# Body-Shield.net
KiCad netlist of a schematic drawn in EAGLE
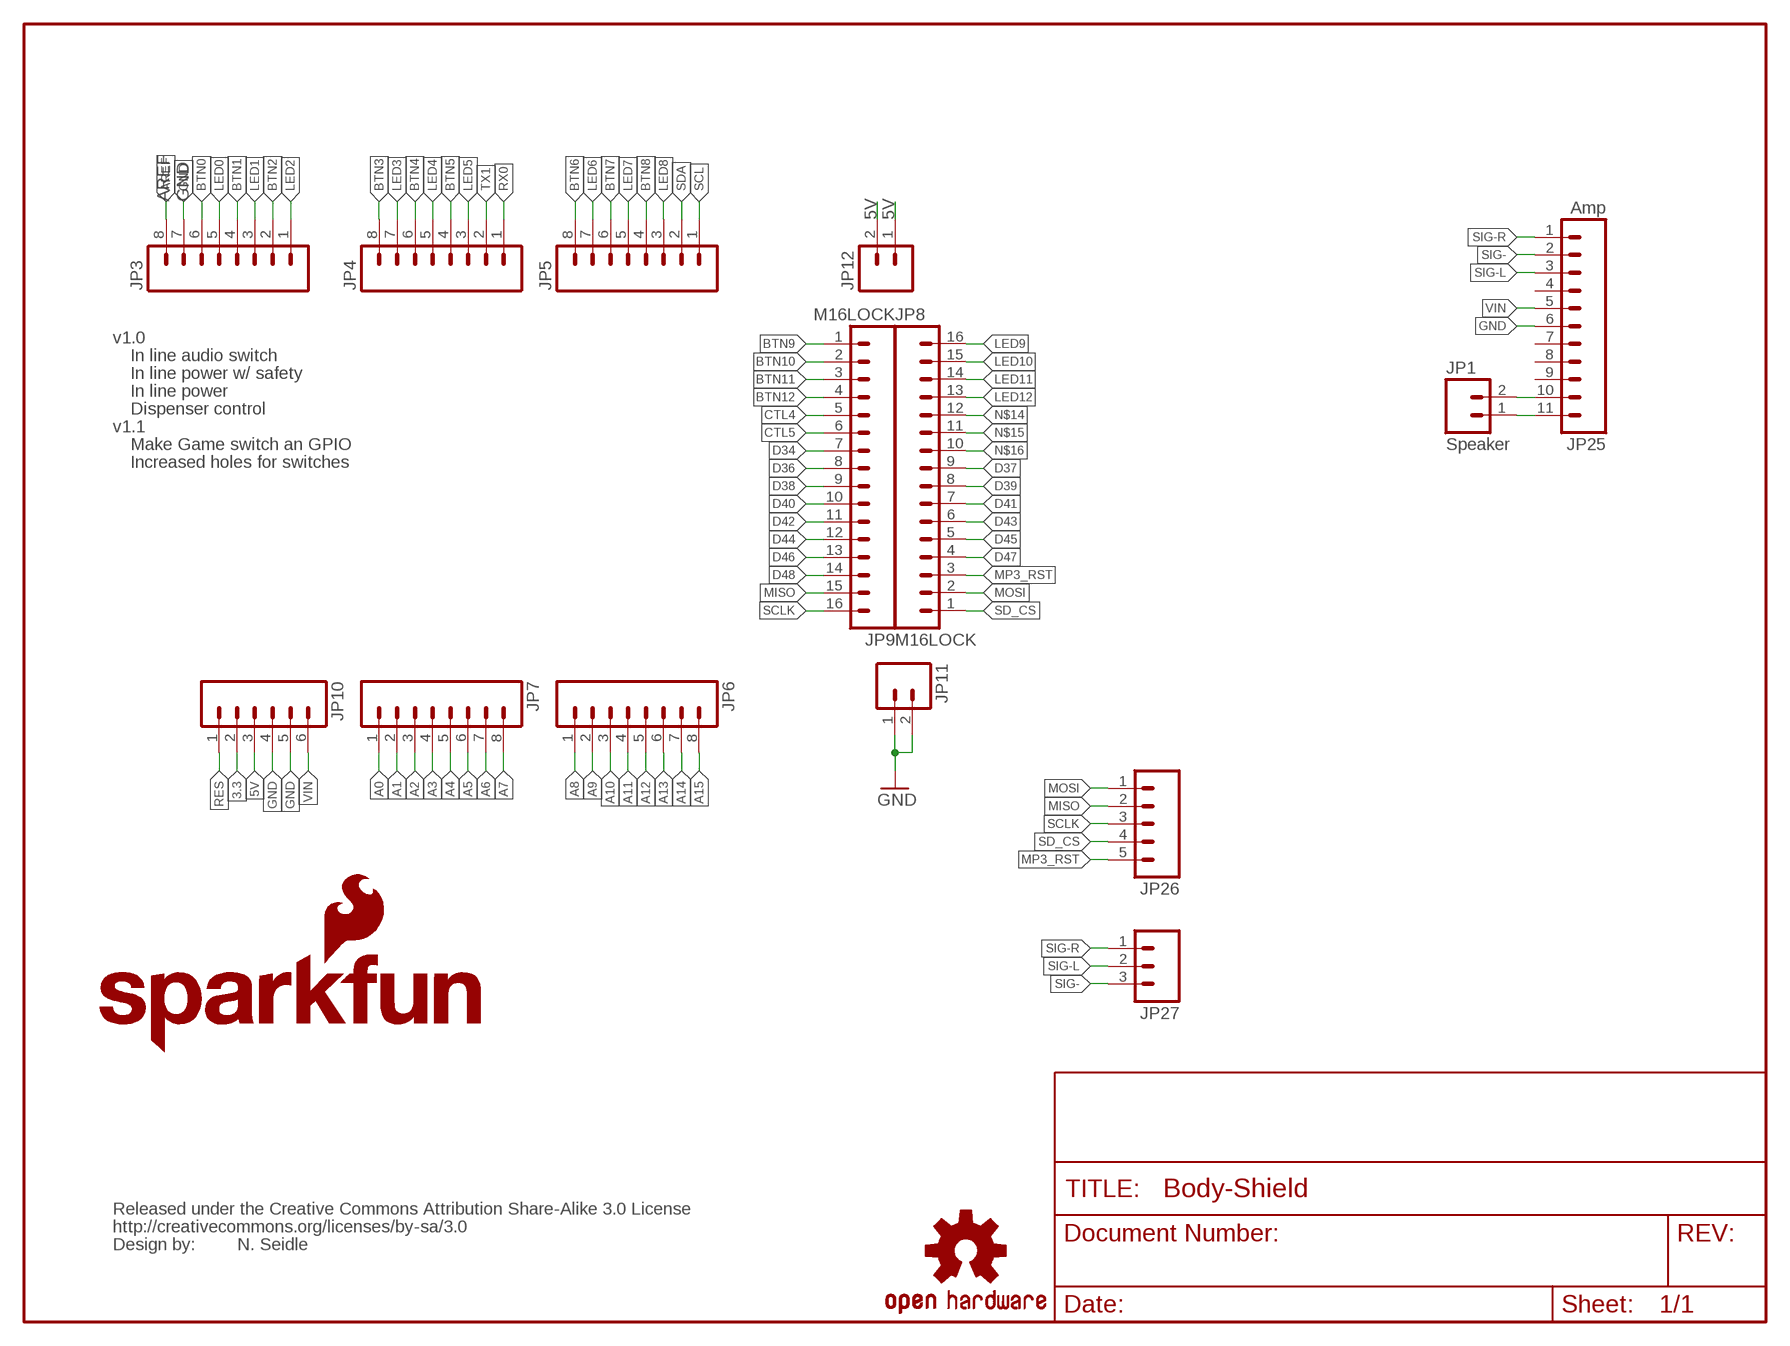
[diagram p0: schematic, sheet 1, part 1 of 2]
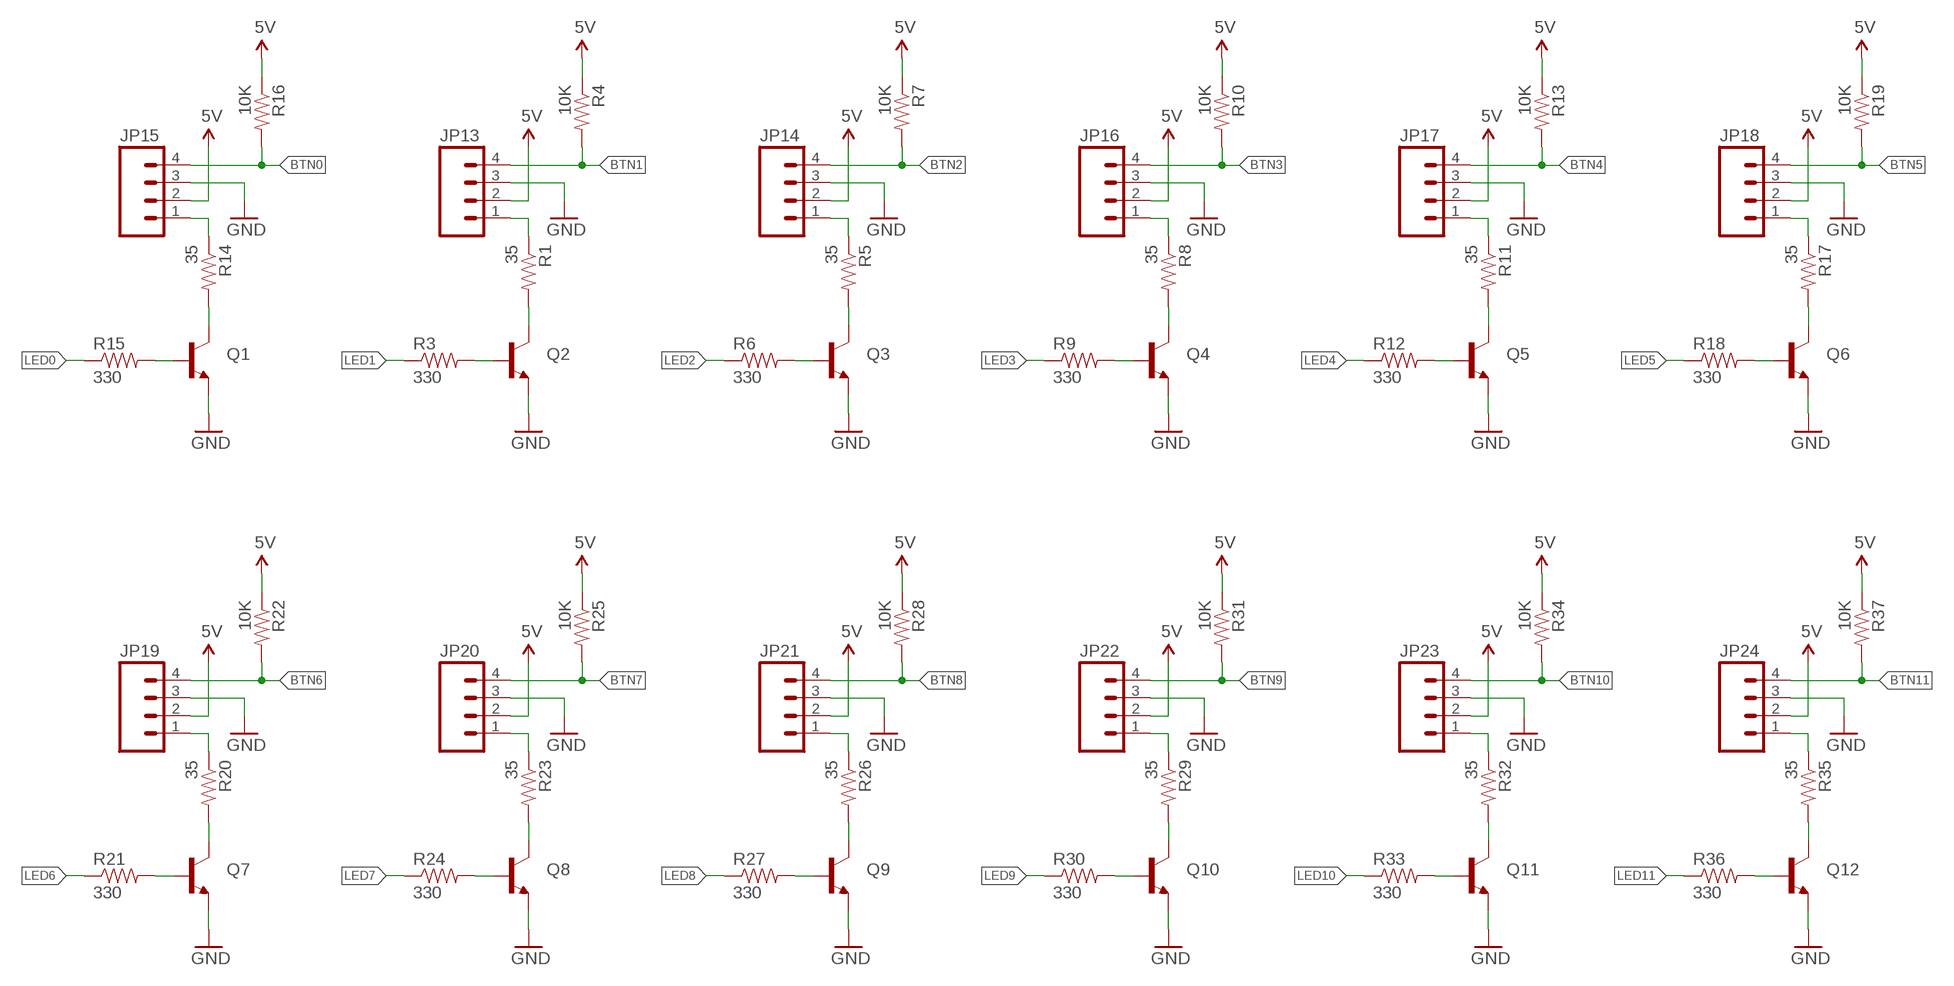
[diagram p1: schematic, sheet 1, part 2 of 2]

(export (version "E")
  (design (tool "Eeschema 10.0.6"))
  (components
    (comp (ref "JP1")
      (value "Speaker")
      (footprint "eagle-import:JST-2-PTH-VERT")
      (libsource (lib "eagle-import") (part "M02JST-PTH-VERT"))
    )
    (comp (ref "JP3")
      (value "M08LOCK")
      (footprint "eagle-import:1X08_LOCK")
      (libsource (lib "eagle-import") (part "M08LOCK"))
    )
    (comp (ref "JP4")
      (value "M08LOCK")
      (footprint "eagle-import:1X08_LOCK")
      (libsource (lib "eagle-import") (part "M08LOCK"))
    )
    (comp (ref "JP5")
      (value "M08LOCK")
      (footprint "eagle-import:1X08_LOCK")
      (libsource (lib "eagle-import") (part "M08LOCK"))
    )
    (comp (ref "JP6")
      (value "M08LOCK")
      (footprint "eagle-import:1X08_LOCK")
      (libsource (lib "eagle-import") (part "M08LOCK"))
    )
    (comp (ref "JP7")
      (value "M08LOCK")
      (footprint "eagle-import:1X08_LOCK")
      (libsource (lib "eagle-import") (part "M08LOCK"))
    )
    (comp (ref "JP8")
      (value "M16LOCK")
      (footprint "eagle-import:1X16_LOCK")
      (libsource (lib "eagle-import") (part "M16LOCK"))
    )
    (comp (ref "JP9")
      (value "M16LOCK")
      (footprint "eagle-import:1X16_LOCK")
      (libsource (lib "eagle-import") (part "M16LOCK"))
    )
    (comp (ref "JP10")
      (value "M06LOCK")
      (footprint "eagle-import:1X06_LOCK")
      (libsource (lib "eagle-import") (part "M06LOCK"))
    )
    (comp (ref "JP11")
      (value "M02LOCK")
      (footprint "eagle-import:1X02_LOCK")
      (libsource (lib "eagle-import") (part "M02LOCK"))
    )
    (comp (ref "JP12")
      (value "M02LOCK")
      (footprint "eagle-import:1X02_LOCK")
      (libsource (lib "eagle-import") (part "M02LOCK"))
    )
    (comp (ref "JP13")
      (value "M04JST-PTH-VERT")
      (footprint "eagle-import:JST-4-PTH-VERT")
      (libsource (lib "eagle-import") (part "M04JST-PTH-VERT"))
    )
    (comp (ref "JP14")
      (value "M04JST-PTH-VERT")
      (footprint "eagle-import:JST-4-PTH-VERT")
      (libsource (lib "eagle-import") (part "M04JST-PTH-VERT"))
    )
    (comp (ref "JP15")
      (value "M04JST-PTH-VERT")
      (footprint "eagle-import:JST-4-PTH-VERT")
      (libsource (lib "eagle-import") (part "M04JST-PTH-VERT"))
    )
    (comp (ref "JP16")
      (value "M04JST-PTH-VERT")
      (footprint "eagle-import:JST-4-PTH-VERT")
      (libsource (lib "eagle-import") (part "M04JST-PTH-VERT"))
    )
    (comp (ref "JP17")
      (value "M04JST-PTH-VERT")
      (footprint "eagle-import:JST-4-PTH-VERT")
      (libsource (lib "eagle-import") (part "M04JST-PTH-VERT"))
    )
    (comp (ref "JP18")
      (value "M04JST-PTH-VERT")
      (footprint "eagle-import:JST-4-PTH-VERT")
      (libsource (lib "eagle-import") (part "M04JST-PTH-VERT"))
    )
    (comp (ref "JP19")
      (value "M04JST-PTH-VERT")
      (footprint "eagle-import:JST-4-PTH-VERT")
      (libsource (lib "eagle-import") (part "M04JST-PTH-VERT"))
    )
    (comp (ref "JP20")
      (value "M04JST-PTH-VERT")
      (footprint "eagle-import:JST-4-PTH-VERT")
      (libsource (lib "eagle-import") (part "M04JST-PTH-VERT"))
    )
    (comp (ref "JP21")
      (value "M04JST-PTH-VERT")
      (footprint "eagle-import:JST-4-PTH-VERT")
      (libsource (lib "eagle-import") (part "M04JST-PTH-VERT"))
    )
    (comp (ref "JP22")
      (value "M04JST-PTH-VERT")
      (footprint "eagle-import:JST-4-PTH-VERT")
      (libsource (lib "eagle-import") (part "M04JST-PTH-VERT"))
    )
    (comp (ref "JP23")
      (value "M04JST-PTH-VERT")
      (footprint "eagle-import:JST-4-PTH-VERT")
      (libsource (lib "eagle-import") (part "M04JST-PTH-VERT"))
    )
    (comp (ref "JP24")
      (value "M04JST-PTH-VERT")
      (footprint "eagle-import:JST-4-PTH-VERT")
      (libsource (lib "eagle-import") (part "M04JST-PTH-VERT"))
    )
    (comp (ref "JP25")
      (value "Amp")
      (footprint "eagle-import:1X11")
      (libsource (lib "eagle-import") (part "M11PTH"))
    )
    (comp (ref "JP26")
      (value "M05JST")
      (footprint "eagle-import:JST-5-PTH")
      (libsource (lib "eagle-import") (part "M05JST"))
    )
    (comp (ref "JP27")
      (value "M03JST-PTH")
      (footprint "eagle-import:JST-3-PTH")
      (libsource (lib "eagle-import") (part "M03JST-PTH"))
    )
    (comp (ref "LOGO1")
      (value "SFE_LOGO_NAME_FLAME.1_INCH")
      (footprint "eagle-import:SFE_LOGO_NAME_FLAME_.1")
      (libsource (lib "eagle-import") (part "SFE_LOGO_NAME_FLAME.1_INCH"))
    )
    (comp (ref "LOGO2")
      (value "OSHW-LOGOS")
      (footprint "eagle-import:OSHW-LOGO-S")
      (libsource (lib "eagle-import") (part "OSHW-LOGOS"))
    )
    (comp (ref "Q1")
      (value "TRANSISTOR_NPN2N3904")
      (footprint "eagle-import:TO-92")
      (libsource (lib "eagle-import") (part "TRANSISTOR_NPN2N3904"))
    )
    (comp (ref "Q2")
      (value "TRANSISTOR_NPN2N3904")
      (footprint "eagle-import:TO-92")
      (libsource (lib "eagle-import") (part "TRANSISTOR_NPN2N3904"))
    )
    (comp (ref "Q3")
      (value "TRANSISTOR_NPN2N3904")
      (footprint "eagle-import:TO-92")
      (libsource (lib "eagle-import") (part "TRANSISTOR_NPN2N3904"))
    )
    (comp (ref "Q4")
      (value "TRANSISTOR_NPN2N3904")
      (footprint "eagle-import:TO-92")
      (libsource (lib "eagle-import") (part "TRANSISTOR_NPN2N3904"))
    )
    (comp (ref "Q5")
      (value "TRANSISTOR_NPN2N3904")
      (footprint "eagle-import:TO-92")
      (libsource (lib "eagle-import") (part "TRANSISTOR_NPN2N3904"))
    )
    (comp (ref "Q6")
      (value "TRANSISTOR_NPN2N3904")
      (footprint "eagle-import:TO-92")
      (libsource (lib "eagle-import") (part "TRANSISTOR_NPN2N3904"))
    )
    (comp (ref "Q7")
      (value "TRANSISTOR_NPN2N3904")
      (footprint "eagle-import:TO-92")
      (libsource (lib "eagle-import") (part "TRANSISTOR_NPN2N3904"))
    )
    (comp (ref "Q8")
      (value "TRANSISTOR_NPN2N3904")
      (footprint "eagle-import:TO-92")
      (libsource (lib "eagle-import") (part "TRANSISTOR_NPN2N3904"))
    )
    (comp (ref "Q9")
      (value "TRANSISTOR_NPN2N3904")
      (footprint "eagle-import:TO-92")
      (libsource (lib "eagle-import") (part "TRANSISTOR_NPN2N3904"))
    )
    (comp (ref "Q10")
      (value "TRANSISTOR_NPN2N3904")
      (footprint "eagle-import:TO-92")
      (libsource (lib "eagle-import") (part "TRANSISTOR_NPN2N3904"))
    )
    (comp (ref "Q11")
      (value "TRANSISTOR_NPN2N3904")
      (footprint "eagle-import:TO-92")
      (libsource (lib "eagle-import") (part "TRANSISTOR_NPN2N3904"))
    )
    (comp (ref "Q12")
      (value "TRANSISTOR_NPN2N3904")
      (footprint "eagle-import:TO-92")
      (libsource (lib "eagle-import") (part "TRANSISTOR_NPN2N3904"))
    )
    (comp (ref "R1")
      (value "35")
      (footprint "eagle-import:AXIAL-0.3")
      (libsource (lib "eagle-import") (part "RESISTORPTH1"))
    )
    (comp (ref "R3")
      (value "330")
      (footprint "eagle-import:AXIAL-0.3")
      (libsource (lib "eagle-import") (part "RESISTORPTH1"))
    )
    (comp (ref "R4")
      (value "10K")
      (footprint "eagle-import:AXIAL-0.3")
      (libsource (lib "eagle-import") (part "RESISTORPTH1"))
    )
    (comp (ref "R5")
      (value "35")
      (footprint "eagle-import:AXIAL-0.3")
      (libsource (lib "eagle-import") (part "RESISTORPTH1"))
    )
    (comp (ref "R6")
      (value "330")
      (footprint "eagle-import:AXIAL-0.3")
      (libsource (lib "eagle-import") (part "RESISTORPTH1"))
    )
    (comp (ref "R7")
      (value "10K")
      (footprint "eagle-import:AXIAL-0.3")
      (libsource (lib "eagle-import") (part "RESISTORPTH1"))
    )
    (comp (ref "R8")
      (value "35")
      (footprint "eagle-import:AXIAL-0.3")
      (libsource (lib "eagle-import") (part "RESISTORPTH1"))
    )
    (comp (ref "R9")
      (value "330")
      (footprint "eagle-import:AXIAL-0.3")
      (libsource (lib "eagle-import") (part "RESISTORPTH1"))
    )
    (comp (ref "R10")
      (value "10K")
      (footprint "eagle-import:AXIAL-0.3")
      (libsource (lib "eagle-import") (part "RESISTORPTH1"))
    )
    (comp (ref "R11")
      (value "35")
      (footprint "eagle-import:AXIAL-0.3")
      (libsource (lib "eagle-import") (part "RESISTORPTH1"))
    )
    (comp (ref "R12")
      (value "330")
      (footprint "eagle-import:AXIAL-0.3")
      (libsource (lib "eagle-import") (part "RESISTORPTH1"))
    )
    (comp (ref "R13")
      (value "10K")
      (footprint "eagle-import:AXIAL-0.3")
      (libsource (lib "eagle-import") (part "RESISTORPTH1"))
    )
    (comp (ref "R14")
      (value "35")
      (footprint "eagle-import:AXIAL-0.3")
      (libsource (lib "eagle-import") (part "RESISTORPTH1"))
    )
    (comp (ref "R15")
      (value "330")
      (footprint "eagle-import:AXIAL-0.3")
      (libsource (lib "eagle-import") (part "RESISTORPTH1"))
    )
    (comp (ref "R16")
      (value "10K")
      (footprint "eagle-import:AXIAL-0.3")
      (libsource (lib "eagle-import") (part "RESISTORPTH1"))
    )
    (comp (ref "R17")
      (value "35")
      (footprint "eagle-import:AXIAL-0.3")
      (libsource (lib "eagle-import") (part "RESISTORPTH1"))
    )
    (comp (ref "R18")
      (value "330")
      (footprint "eagle-import:AXIAL-0.3")
      (libsource (lib "eagle-import") (part "RESISTORPTH1"))
    )
    (comp (ref "R19")
      (value "10K")
      (footprint "eagle-import:AXIAL-0.3")
      (libsource (lib "eagle-import") (part "RESISTORPTH1"))
    )
    (comp (ref "R20")
      (value "35")
      (footprint "eagle-import:AXIAL-0.3")
      (libsource (lib "eagle-import") (part "RESISTORPTH1"))
    )
    (comp (ref "R21")
      (value "330")
      (footprint "eagle-import:AXIAL-0.3")
      (libsource (lib "eagle-import") (part "RESISTORPTH1"))
    )
    (comp (ref "R22")
      (value "10K")
      (footprint "eagle-import:AXIAL-0.3")
      (libsource (lib "eagle-import") (part "RESISTORPTH1"))
    )
    (comp (ref "R23")
      (value "35")
      (footprint "eagle-import:AXIAL-0.3")
      (libsource (lib "eagle-import") (part "RESISTORPTH1"))
    )
    (comp (ref "R24")
      (value "330")
      (footprint "eagle-import:AXIAL-0.3")
      (libsource (lib "eagle-import") (part "RESISTORPTH1"))
    )
    (comp (ref "R25")
      (value "10K")
      (footprint "eagle-import:AXIAL-0.3")
      (libsource (lib "eagle-import") (part "RESISTORPTH1"))
    )
    (comp (ref "R26")
      (value "35")
      (footprint "eagle-import:AXIAL-0.3")
      (libsource (lib "eagle-import") (part "RESISTORPTH1"))
    )
    (comp (ref "R27")
      (value "330")
      (footprint "eagle-import:AXIAL-0.3")
      (libsource (lib "eagle-import") (part "RESISTORPTH1"))
    )
    (comp (ref "R28")
      (value "10K")
      (footprint "eagle-import:AXIAL-0.3")
      (libsource (lib "eagle-import") (part "RESISTORPTH1"))
    )
    (comp (ref "R29")
      (value "35")
      (footprint "eagle-import:AXIAL-0.3")
      (libsource (lib "eagle-import") (part "RESISTORPTH1"))
    )
    (comp (ref "R30")
      (value "330")
      (footprint "eagle-import:AXIAL-0.3")
      (libsource (lib "eagle-import") (part "RESISTORPTH1"))
    )
    (comp (ref "R31")
      (value "10K")
      (footprint "eagle-import:AXIAL-0.3")
      (libsource (lib "eagle-import") (part "RESISTORPTH1"))
    )
    (comp (ref "R32")
      (value "35")
      (footprint "eagle-import:AXIAL-0.3")
      (libsource (lib "eagle-import") (part "RESISTORPTH1"))
    )
    (comp (ref "R33")
      (value "330")
      (footprint "eagle-import:AXIAL-0.3")
      (libsource (lib "eagle-import") (part "RESISTORPTH1"))
    )
    (comp (ref "R34")
      (value "10K")
      (footprint "eagle-import:AXIAL-0.3")
      (libsource (lib "eagle-import") (part "RESISTORPTH1"))
    )
    (comp (ref "R35")
      (value "35")
      (footprint "eagle-import:AXIAL-0.3")
      (libsource (lib "eagle-import") (part "RESISTORPTH1"))
    )
    (comp (ref "R36")
      (value "330")
      (footprint "eagle-import:AXIAL-0.3")
      (libsource (lib "eagle-import") (part "RESISTORPTH1"))
    )
    (comp (ref "R37")
      (value "10K")
      (footprint "eagle-import:AXIAL-0.3")
      (libsource (lib "eagle-import") (part "RESISTORPTH1"))
    )
    (comp (ref "U$2")
      (value "CREATIVE_COMMONS")
      (footprint "eagle-import:CREATIVE_COMMONS")
      (libsource (lib "eagle-import") (part "CREATIVE_COMMONS"))
    )
  )
  (nets
    (net (code "1") (name "3.3") (class "Default")
      (node (ref "JP10") (pin "2") (pinfunction "2_2") (pintype "passive"))
    )
    (net (code "2") (name "5V") (class "Default")
      (node (ref "JP10") (pin "3") (pinfunction "3_3") (pintype "passive"))
      (node (ref "JP12") (pin "1") (pinfunction "1_1") (pintype "passive"))
      (node (ref "JP12") (pin "2") (pinfunction "2_2") (pintype "passive"))
      (node (ref "JP13") (pin "2") (pinfunction "2_2") (pintype "passive"))
      (node (ref "JP14") (pin "2") (pinfunction "2_2") (pintype "passive"))
      (node (ref "JP15") (pin "2") (pinfunction "2_2") (pintype "passive"))
      (node (ref "JP16") (pin "2") (pinfunction "2_2") (pintype "passive"))
      (node (ref "JP17") (pin "2") (pinfunction "2_2") (pintype "passive"))
      (node (ref "JP18") (pin "2") (pinfunction "2_2") (pintype "passive"))
      (node (ref "JP19") (pin "2") (pinfunction "2_2") (pintype "passive"))
      (node (ref "JP20") (pin "2") (pinfunction "2_2") (pintype "passive"))
      (node (ref "JP21") (pin "2") (pinfunction "2_2") (pintype "passive"))
      (node (ref "JP22") (pin "2") (pinfunction "2_2") (pintype "passive"))
      (node (ref "JP23") (pin "2") (pinfunction "2_2") (pintype "passive"))
      (node (ref "JP24") (pin "2") (pinfunction "2_2") (pintype "passive"))
      (node (ref "R10") (pin "P$1") (pinfunction "1_P$1") (pintype "passive"))
      (node (ref "R13") (pin "P$1") (pinfunction "1_P$1") (pintype "passive"))
      (node (ref "R16") (pin "P$1") (pinfunction "1_P$1") (pintype "passive"))
      (node (ref "R19") (pin "P$1") (pinfunction "1_P$1") (pintype "passive"))
      (node (ref "R22") (pin "P$1") (pinfunction "1_P$1") (pintype "passive"))
      (node (ref "R25") (pin "P$1") (pinfunction "1_P$1") (pintype "passive"))
      (node (ref "R28") (pin "P$1") (pinfunction "1_P$1") (pintype "passive"))
      (node (ref "R31") (pin "P$1") (pinfunction "1_P$1") (pintype "passive"))
      (node (ref "R34") (pin "P$1") (pinfunction "1_P$1") (pintype "passive"))
      (node (ref "R37") (pin "P$1") (pinfunction "1_P$1") (pintype "passive"))
      (node (ref "R4") (pin "P$1") (pinfunction "1_P$1") (pintype "passive"))
      (node (ref "R7") (pin "P$1") (pinfunction "1_P$1") (pintype "passive"))
    )
    (net (code "3") (name "A0") (class "Default")
      (node (ref "JP7") (pin "1") (pinfunction "1_1") (pintype "passive"))
    )
    (net (code "4") (name "A1") (class "Default")
      (node (ref "JP7") (pin "2") (pinfunction "2_2") (pintype "passive"))
    )
    (net (code "5") (name "A2") (class "Default")
      (node (ref "JP7") (pin "3") (pinfunction "3_3") (pintype "passive"))
    )
    (net (code "6") (name "A3") (class "Default")
      (node (ref "JP7") (pin "4") (pinfunction "4_4") (pintype "passive"))
    )
    (net (code "7") (name "A4") (class "Default")
      (node (ref "JP7") (pin "5") (pinfunction "5_5") (pintype "passive"))
    )
    (net (code "8") (name "A5") (class "Default")
      (node (ref "JP7") (pin "6") (pinfunction "6_6") (pintype "passive"))
    )
    (net (code "9") (name "A6") (class "Default")
      (node (ref "JP7") (pin "7") (pinfunction "7_7") (pintype "passive"))
    )
    (net (code "10") (name "A7") (class "Default")
      (node (ref "JP7") (pin "8") (pinfunction "8_8") (pintype "passive"))
    )
    (net (code "11") (name "A8") (class "Default")
      (node (ref "JP6") (pin "1") (pinfunction "1_1") (pintype "passive"))
    )
    (net (code "12") (name "A9") (class "Default")
      (node (ref "JP6") (pin "2") (pinfunction "2_2") (pintype "passive"))
    )
    (net (code "13") (name "A10") (class "Default")
      (node (ref "JP6") (pin "3") (pinfunction "3_3") (pintype "passive"))
    )
    (net (code "14") (name "A11") (class "Default")
      (node (ref "JP6") (pin "4") (pinfunction "4_4") (pintype "passive"))
    )
    (net (code "15") (name "A12") (class "Default")
      (node (ref "JP6") (pin "5") (pinfunction "5_5") (pintype "passive"))
    )
    (net (code "16") (name "A13") (class "Default")
      (node (ref "JP6") (pin "6") (pinfunction "6_6") (pintype "passive"))
    )
    (net (code "17") (name "A14") (class "Default")
      (node (ref "JP6") (pin "7") (pinfunction "7_7") (pintype "passive"))
    )
    (net (code "18") (name "A15") (class "Default")
      (node (ref "JP6") (pin "8") (pinfunction "8_8") (pintype "passive"))
    )
    (net (code "19") (name "AREF") (class "Default")
      (node (ref "JP3") (pin "8") (pinfunction "8_8") (pintype "passive"))
    )
    (net (code "20") (name "BTN0") (class "Default")
      (node (ref "JP15") (pin "4") (pinfunction "4_4") (pintype "passive"))
      (node (ref "JP3") (pin "6") (pinfunction "6_6") (pintype "passive"))
      (node (ref "R16") (pin "P$2") (pinfunction "2_P$2") (pintype "passive"))
    )
    (net (code "21") (name "BTN1") (class "Default")
      (node (ref "JP13") (pin "4") (pinfunction "4_4") (pintype "passive"))
      (node (ref "JP3") (pin "4") (pinfunction "4_4") (pintype "passive"))
      (node (ref "R4") (pin "P$2") (pinfunction "2_P$2") (pintype "passive"))
    )
    (net (code "22") (name "BTN2") (class "Default")
      (node (ref "JP14") (pin "4") (pinfunction "4_4") (pintype "passive"))
      (node (ref "JP3") (pin "2") (pinfunction "2_2") (pintype "passive"))
      (node (ref "R7") (pin "P$2") (pinfunction "2_P$2") (pintype "passive"))
    )
    (net (code "23") (name "BTN3") (class "Default")
      (node (ref "JP16") (pin "4") (pinfunction "4_4") (pintype "passive"))
      (node (ref "JP4") (pin "8") (pinfunction "8_8") (pintype "passive"))
      (node (ref "R10") (pin "P$2") (pinfunction "2_P$2") (pintype "passive"))
    )
    (net (code "24") (name "BTN4") (class "Default")
      (node (ref "JP17") (pin "4") (pinfunction "4_4") (pintype "passive"))
      (node (ref "JP4") (pin "6") (pinfunction "6_6") (pintype "passive"))
      (node (ref "R13") (pin "P$2") (pinfunction "2_P$2") (pintype "passive"))
    )
    (net (code "25") (name "BTN5") (class "Default")
      (node (ref "JP18") (pin "4") (pinfunction "4_4") (pintype "passive"))
      (node (ref "JP4") (pin "4") (pinfunction "4_4") (pintype "passive"))
      (node (ref "R19") (pin "P$2") (pinfunction "2_P$2") (pintype "passive"))
    )
    (net (code "26") (name "BTN6") (class "Default")
      (node (ref "JP19") (pin "4") (pinfunction "4_4") (pintype "passive"))
      (node (ref "JP5") (pin "8") (pinfunction "8_8") (pintype "passive"))
      (node (ref "R22") (pin "P$2") (pinfunction "2_P$2") (pintype "passive"))
    )
    (net (code "27") (name "BTN7") (class "Default")
      (node (ref "JP20") (pin "4") (pinfunction "4_4") (pintype "passive"))
      (node (ref "JP5") (pin "6") (pinfunction "6_6") (pintype "passive"))
      (node (ref "R25") (pin "P$2") (pinfunction "2_P$2") (pintype "passive"))
    )
    (net (code "28") (name "BTN8") (class "Default")
      (node (ref "JP21") (pin "4") (pinfunction "4_4") (pintype "passive"))
      (node (ref "JP5") (pin "4") (pinfunction "4_4") (pintype "passive"))
      (node (ref "R28") (pin "P$2") (pinfunction "2_P$2") (pintype "passive"))
    )
    (net (code "29") (name "BTN9") (class "Default")
      (node (ref "JP22") (pin "4") (pinfunction "4_4") (pintype "passive"))
      (node (ref "JP9") (pin "1") (pinfunction "1_1") (pintype "passive"))
      (node (ref "R31") (pin "P$2") (pinfunction "2_P$2") (pintype "passive"))
    )
    (net (code "30") (name "BTN10") (class "Default")
      (node (ref "JP23") (pin "4") (pinfunction "4_4") (pintype "passive"))
      (node (ref "JP9") (pin "2") (pinfunction "2_2") (pintype "passive"))
      (node (ref "R34") (pin "P$2") (pinfunction "2_P$2") (pintype "passive"))
    )
    (net (code "31") (name "BTN11") (class "Default")
      (node (ref "JP24") (pin "4") (pinfunction "4_4") (pintype "passive"))
      (node (ref "JP9") (pin "3") (pinfunction "3_3") (pintype "passive"))
      (node (ref "R37") (pin "P$2") (pinfunction "2_P$2") (pintype "passive"))
    )
    (net (code "32") (name "BTN12") (class "Default")
      (node (ref "JP9") (pin "4") (pinfunction "4_4") (pintype "passive"))
    )
    (net (code "33") (name "CTL4") (class "Default")
      (node (ref "JP9") (pin "5") (pinfunction "5_5") (pintype "passive"))
    )
    (net (code "34") (name "CTL5") (class "Default")
      (node (ref "JP9") (pin "6") (pinfunction "6_6") (pintype "passive"))
    )
    (net (code "35") (name "D34") (class "Default")
      (node (ref "JP9") (pin "7") (pinfunction "7_7") (pintype "passive"))
    )
    (net (code "36") (name "D36") (class "Default")
      (node (ref "JP9") (pin "8") (pinfunction "8_8") (pintype "passive"))
    )
    (net (code "37") (name "D37") (class "Default")
      (node (ref "JP8") (pin "9") (pinfunction "9_9") (pintype "passive"))
    )
    (net (code "38") (name "D38") (class "Default")
      (node (ref "JP9") (pin "9") (pinfunction "9_9") (pintype "passive"))
    )
    (net (code "39") (name "D39") (class "Default")
      (node (ref "JP8") (pin "8") (pinfunction "8_8") (pintype "passive"))
    )
    (net (code "40") (name "D40") (class "Default")
      (node (ref "JP9") (pin "10") (pinfunction "10_10") (pintype "passive"))
    )
    (net (code "41") (name "D41") (class "Default")
      (node (ref "JP8") (pin "7") (pinfunction "7_7") (pintype "passive"))
    )
    (net (code "42") (name "D42") (class "Default")
      (node (ref "JP9") (pin "11") (pinfunction "11_11") (pintype "passive"))
    )
    (net (code "43") (name "D43") (class "Default")
      (node (ref "JP8") (pin "6") (pinfunction "6_6") (pintype "passive"))
    )
    (net (code "44") (name "D44") (class "Default")
      (node (ref "JP9") (pin "12") (pinfunction "12_12") (pintype "passive"))
    )
    (net (code "45") (name "D45") (class "Default")
      (node (ref "JP8") (pin "5") (pinfunction "5_5") (pintype "passive"))
    )
    (net (code "46") (name "D46") (class "Default")
      (node (ref "JP9") (pin "13") (pinfunction "13_13") (pintype "passive"))
    )
    (net (code "47") (name "D47") (class "Default")
      (node (ref "JP8") (pin "4") (pinfunction "4_4") (pintype "passive"))
    )
    (net (code "48") (name "D48") (class "Default")
      (node (ref "JP9") (pin "14") (pinfunction "14_14") (pintype "passive"))
    )
    (net (code "49") (name "GND") (class "Default")
      (node (ref "JP10") (pin "4") (pinfunction "4_4") (pintype "passive"))
      (node (ref "JP10") (pin "5") (pinfunction "5_5") (pintype "passive"))
      (node (ref "JP11") (pin "1") (pinfunction "1_1") (pintype "passive"))
      (node (ref "JP11") (pin "2") (pinfunction "2_2") (pintype "passive"))
      (node (ref "JP13") (pin "3") (pinfunction "3_3") (pintype "passive"))
      (node (ref "JP14") (pin "3") (pinfunction "3_3") (pintype "passive"))
      (node (ref "JP15") (pin "3") (pinfunction "3_3") (pintype "passive"))
      (node (ref "JP16") (pin "3") (pinfunction "3_3") (pintype "passive"))
      (node (ref "JP17") (pin "3") (pinfunction "3_3") (pintype "passive"))
      (node (ref "JP18") (pin "3") (pinfunction "3_3") (pintype "passive"))
      (node (ref "JP19") (pin "3") (pinfunction "3_3") (pintype "passive"))
      (node (ref "JP20") (pin "3") (pinfunction "3_3") (pintype "passive"))
      (node (ref "JP21") (pin "3") (pinfunction "3_3") (pintype "passive"))
      (node (ref "JP22") (pin "3") (pinfunction "3_3") (pintype "passive"))
      (node (ref "JP23") (pin "3") (pinfunction "3_3") (pintype "passive"))
      (node (ref "JP24") (pin "3") (pinfunction "3_3") (pintype "passive"))
      (node (ref "JP25") (pin "6") (pinfunction "6_6") (pintype "passive"))
      (node (ref "JP3") (pin "7") (pinfunction "7_7") (pintype "passive"))
      (node (ref "Q1") (pin "1") (pinfunction "E_1") (pintype "passive"))
      (node (ref "Q10") (pin "1") (pinfunction "E_1") (pintype "passive"))
      (node (ref "Q11") (pin "1") (pinfunction "E_1") (pintype "passive"))
      (node (ref "Q12") (pin "1") (pinfunction "E_1") (pintype "passive"))
      (node (ref "Q2") (pin "1") (pinfunction "E_1") (pintype "passive"))
      (node (ref "Q3") (pin "1") (pinfunction "E_1") (pintype "passive"))
      (node (ref "Q4") (pin "1") (pinfunction "E_1") (pintype "passive"))
      (node (ref "Q5") (pin "1") (pinfunction "E_1") (pintype "passive"))
      (node (ref "Q6") (pin "1") (pinfunction "E_1") (pintype "passive"))
      (node (ref "Q7") (pin "1") (pinfunction "E_1") (pintype "passive"))
      (node (ref "Q8") (pin "1") (pinfunction "E_1") (pintype "passive"))
      (node (ref "Q9") (pin "1") (pinfunction "E_1") (pintype "passive"))
    )
    (net (code "50") (name "LED0") (class "Default")
      (node (ref "JP3") (pin "5") (pinfunction "5_5") (pintype "passive"))
      (node (ref "R15") (pin "P$1") (pinfunction "1_P$1") (pintype "passive"))
    )
    (net (code "51") (name "LED1") (class "Default")
      (node (ref "JP3") (pin "3") (pinfunction "3_3") (pintype "passive"))
      (node (ref "R3") (pin "P$1") (pinfunction "1_P$1") (pintype "passive"))
    )
    (net (code "52") (name "LED2") (class "Default")
      (node (ref "JP3") (pin "1") (pinfunction "1_1") (pintype "passive"))
      (node (ref "R6") (pin "P$1") (pinfunction "1_P$1") (pintype "passive"))
    )
    (net (code "53") (name "LED3") (class "Default")
      (node (ref "JP4") (pin "7") (pinfunction "7_7") (pintype "passive"))
      (node (ref "R9") (pin "P$1") (pinfunction "1_P$1") (pintype "passive"))
    )
    (net (code "54") (name "LED4") (class "Default")
      (node (ref "JP4") (pin "5") (pinfunction "5_5") (pintype "passive"))
      (node (ref "R12") (pin "P$1") (pinfunction "1_P$1") (pintype "passive"))
    )
    (net (code "55") (name "LED5") (class "Default")
      (node (ref "JP4") (pin "3") (pinfunction "3_3") (pintype "passive"))
      (node (ref "R18") (pin "P$1") (pinfunction "1_P$1") (pintype "passive"))
    )
    (net (code "56") (name "LED6") (class "Default")
      (node (ref "JP5") (pin "7") (pinfunction "7_7") (pintype "passive"))
      (node (ref "R21") (pin "P$1") (pinfunction "1_P$1") (pintype "passive"))
    )
    (net (code "57") (name "LED7") (class "Default")
      (node (ref "JP5") (pin "5") (pinfunction "5_5") (pintype "passive"))
      (node (ref "R24") (pin "P$1") (pinfunction "1_P$1") (pintype "passive"))
    )
    (net (code "58") (name "LED8") (class "Default")
      (node (ref "JP5") (pin "3") (pinfunction "3_3") (pintype "passive"))
      (node (ref "R27") (pin "P$1") (pinfunction "1_P$1") (pintype "passive"))
    )
    (net (code "59") (name "LED9") (class "Default")
      (node (ref "JP8") (pin "16") (pinfunction "16_16") (pintype "passive"))
      (node (ref "R30") (pin "P$1") (pinfunction "1_P$1") (pintype "passive"))
    )
    (net (code "60") (name "LED10") (class "Default")
      (node (ref "JP8") (pin "15") (pinfunction "15_15") (pintype "passive"))
      (node (ref "R33") (pin "P$1") (pinfunction "1_P$1") (pintype "passive"))
    )
    (net (code "61") (name "LED11") (class "Default")
      (node (ref "JP8") (pin "14") (pinfunction "14_14") (pintype "passive"))
      (node (ref "R36") (pin "P$1") (pinfunction "1_P$1") (pintype "passive"))
    )
    (net (code "62") (name "LED12") (class "Default")
      (node (ref "JP8") (pin "13") (pinfunction "13_13") (pintype "passive"))
    )
    (net (code "63") (name "MISO") (class "Default")
      (node (ref "JP26") (pin "2") (pinfunction "2_2") (pintype "passive"))
      (node (ref "JP9") (pin "15") (pinfunction "15_15") (pintype "passive"))
    )
    (net (code "64") (name "MOSI") (class "Default")
      (node (ref "JP26") (pin "1") (pinfunction "1_1") (pintype "passive"))
      (node (ref "JP8") (pin "2") (pinfunction "2_2") (pintype "passive"))
    )
    (net (code "65") (name "MP3_RST") (class "Default")
      (node (ref "JP26") (pin "5") (pinfunction "5_5") (pintype "passive"))
      (node (ref "JP8") (pin "3") (pinfunction "3_3") (pintype "passive"))
    )
    (net (code "66") (name "N$14") (class "Default")
      (node (ref "JP8") (pin "12") (pinfunction "12_12") (pintype "passive"))
    )
    (net (code "67") (name "N$15") (class "Default")
      (node (ref "JP8") (pin "11") (pinfunction "11_11") (pintype "passive"))
    )
    (net (code "68") (name "N$16") (class "Default")
      (node (ref "JP8") (pin "10") (pinfunction "10_10") (pintype "passive"))
    )
    (net (code "69") (name "Net-(JP1-Pad1)") (class "Default")
      (node (ref "JP1") (pin "1") (pinfunction "1_1") (pintype "passive"))
      (node (ref "JP25") (pin "11") (pinfunction "11_11") (pintype "passive"))
    )
    (net (code "70") (name "Net-(JP1-Pad2)") (class "Default")
      (node (ref "JP1") (pin "2") (pinfunction "2_2") (pintype "passive"))
      (node (ref "JP25") (pin "10") (pinfunction "10_10") (pintype "passive"))
    )
    (net (code "71") (name "Net-(Q1-B)") (class "Default")
      (node (ref "Q1") (pin "2") (pinfunction "B_2") (pintype "passive"))
      (node (ref "R15") (pin "P$2") (pinfunction "2_P$2") (pintype "passive"))
    )
    (net (code "72") (name "Net-(Q1-C)") (class "Default")
      (node (ref "Q1") (pin "3") (pinfunction "C_3") (pintype "passive"))
      (node (ref "R14") (pin "P$2") (pinfunction "2_P$2") (pintype "passive"))
    )
    (net (code "73") (name "Net-(Q2-B)") (class "Default")
      (node (ref "Q2") (pin "2") (pinfunction "B_2") (pintype "passive"))
      (node (ref "R3") (pin "P$2") (pinfunction "2_P$2") (pintype "passive"))
    )
    (net (code "74") (name "Net-(Q2-C)") (class "Default")
      (node (ref "Q2") (pin "3") (pinfunction "C_3") (pintype "passive"))
      (node (ref "R1") (pin "P$2") (pinfunction "2_P$2") (pintype "passive"))
    )
    (net (code "75") (name "Net-(Q3-B)") (class "Default")
      (node (ref "Q3") (pin "2") (pinfunction "B_2") (pintype "passive"))
      (node (ref "R6") (pin "P$2") (pinfunction "2_P$2") (pintype "passive"))
    )
    (net (code "76") (name "Net-(Q3-C)") (class "Default")
      (node (ref "Q3") (pin "3") (pinfunction "C_3") (pintype "passive"))
      (node (ref "R5") (pin "P$2") (pinfunction "2_P$2") (pintype "passive"))
    )
    (net (code "77") (name "Net-(Q4-B)") (class "Default")
      (node (ref "Q4") (pin "2") (pinfunction "B_2") (pintype "passive"))
      (node (ref "R9") (pin "P$2") (pinfunction "2_P$2") (pintype "passive"))
    )
    (net (code "78") (name "Net-(Q4-C)") (class "Default")
      (node (ref "Q4") (pin "3") (pinfunction "C_3") (pintype "passive"))
      (node (ref "R8") (pin "P$2") (pinfunction "2_P$2") (pintype "passive"))
    )
    (net (code "79") (name "Net-(Q5-B)") (class "Default")
      (node (ref "Q5") (pin "2") (pinfunction "B_2") (pintype "passive"))
      (node (ref "R12") (pin "P$2") (pinfunction "2_P$2") (pintype "passive"))
    )
    (net (code "80") (name "Net-(Q5-C)") (class "Default")
      (node (ref "Q5") (pin "3") (pinfunction "C_3") (pintype "passive"))
      (node (ref "R11") (pin "P$2") (pinfunction "2_P$2") (pintype "passive"))
    )
    (net (code "81") (name "Net-(Q6-B)") (class "Default")
      (node (ref "Q6") (pin "2") (pinfunction "B_2") (pintype "passive"))
      (node (ref "R18") (pin "P$2") (pinfunction "2_P$2") (pintype "passive"))
    )
    (net (code "82") (name "Net-(Q6-C)") (class "Default")
      (node (ref "Q6") (pin "3") (pinfunction "C_3") (pintype "passive"))
      (node (ref "R17") (pin "P$2") (pinfunction "2_P$2") (pintype "passive"))
    )
    (net (code "83") (name "Net-(Q7-B)") (class "Default")
      (node (ref "Q7") (pin "2") (pinfunction "B_2") (pintype "passive"))
      (node (ref "R21") (pin "P$2") (pinfunction "2_P$2") (pintype "passive"))
    )
    (net (code "84") (name "Net-(Q7-C)") (class "Default")
      (node (ref "Q7") (pin "3") (pinfunction "C_3") (pintype "passive"))
      (node (ref "R20") (pin "P$2") (pinfunction "2_P$2") (pintype "passive"))
    )
    (net (code "85") (name "Net-(Q8-B)") (class "Default")
      (node (ref "Q8") (pin "2") (pinfunction "B_2") (pintype "passive"))
      (node (ref "R24") (pin "P$2") (pinfunction "2_P$2") (pintype "passive"))
    )
    (net (code "86") (name "Net-(Q8-C)") (class "Default")
      (node (ref "Q8") (pin "3") (pinfunction "C_3") (pintype "passive"))
      (node (ref "R23") (pin "P$2") (pinfunction "2_P$2") (pintype "passive"))
    )
    (net (code "87") (name "Net-(Q9-B)") (class "Default")
      (node (ref "Q9") (pin "2") (pinfunction "B_2") (pintype "passive"))
      (node (ref "R27") (pin "P$2") (pinfunction "2_P$2") (pintype "passive"))
    )
    (net (code "88") (name "Net-(Q9-C)") (class "Default")
      (node (ref "Q9") (pin "3") (pinfunction "C_3") (pintype "passive"))
      (node (ref "R26") (pin "P$2") (pinfunction "2_P$2") (pintype "passive"))
    )
    (net (code "89") (name "Net-(Q10-B)") (class "Default")
      (node (ref "Q10") (pin "2") (pinfunction "B_2") (pintype "passive"))
      (node (ref "R30") (pin "P$2") (pinfunction "2_P$2") (pintype "passive"))
    )
    (net (code "90") (name "Net-(Q10-C)") (class "Default")
      (node (ref "Q10") (pin "3") (pinfunction "C_3") (pintype "passive"))
      (node (ref "R29") (pin "P$2") (pinfunction "2_P$2") (pintype "passive"))
    )
    (net (code "91") (name "Net-(Q11-B)") (class "Default")
      (node (ref "Q11") (pin "2") (pinfunction "B_2") (pintype "passive"))
      (node (ref "R33") (pin "P$2") (pinfunction "2_P$2") (pintype "passive"))
    )
    (net (code "92") (name "Net-(Q11-C)") (class "Default")
      (node (ref "Q11") (pin "3") (pinfunction "C_3") (pintype "passive"))
      (node (ref "R32") (pin "P$2") (pinfunction "2_P$2") (pintype "passive"))
    )
    (net (code "93") (name "Net-(Q12-B)") (class "Default")
      (node (ref "Q12") (pin "2") (pinfunction "B_2") (pintype "passive"))
      (node (ref "R36") (pin "P$2") (pinfunction "2_P$2") (pintype "passive"))
    )
    (net (code "94") (name "Net-(Q12-C)") (class "Default")
      (node (ref "Q12") (pin "3") (pinfunction "C_3") (pintype "passive"))
      (node (ref "R35") (pin "P$2") (pinfunction "2_P$2") (pintype "passive"))
    )
    (net (code "95") (name "Net-(R1-1)") (class "Default")
      (node (ref "JP13") (pin "1") (pinfunction "1_1") (pintype "passive"))
      (node (ref "R1") (pin "P$1") (pinfunction "1_P$1") (pintype "passive"))
    )
    (net (code "96") (name "Net-(R5-1)") (class "Default")
      (node (ref "JP14") (pin "1") (pinfunction "1_1") (pintype "passive"))
      (node (ref "R5") (pin "P$1") (pinfunction "1_P$1") (pintype "passive"))
    )
    (net (code "97") (name "Net-(R8-1)") (class "Default")
      (node (ref "JP16") (pin "1") (pinfunction "1_1") (pintype "passive"))
      (node (ref "R8") (pin "P$1") (pinfunction "1_P$1") (pintype "passive"))
    )
    (net (code "98") (name "Net-(R11-1)") (class "Default")
      (node (ref "JP17") (pin "1") (pinfunction "1_1") (pintype "passive"))
      (node (ref "R11") (pin "P$1") (pinfunction "1_P$1") (pintype "passive"))
    )
    (net (code "99") (name "Net-(R14-1)") (class "Default")
      (node (ref "JP15") (pin "1") (pinfunction "1_1") (pintype "passive"))
      (node (ref "R14") (pin "P$1") (pinfunction "1_P$1") (pintype "passive"))
    )
    (net (code "100") (name "Net-(R17-1)") (class "Default")
      (node (ref "JP18") (pin "1") (pinfunction "1_1") (pintype "passive"))
      (node (ref "R17") (pin "P$1") (pinfunction "1_P$1") (pintype "passive"))
    )
    (net (code "101") (name "Net-(R20-1)") (class "Default")
      (node (ref "JP19") (pin "1") (pinfunction "1_1") (pintype "passive"))
      (node (ref "R20") (pin "P$1") (pinfunction "1_P$1") (pintype "passive"))
    )
    (net (code "102") (name "Net-(R23-1)") (class "Default")
      (node (ref "JP20") (pin "1") (pinfunction "1_1") (pintype "passive"))
      (node (ref "R23") (pin "P$1") (pinfunction "1_P$1") (pintype "passive"))
    )
    (net (code "103") (name "Net-(R26-1)") (class "Default")
      (node (ref "JP21") (pin "1") (pinfunction "1_1") (pintype "passive"))
      (node (ref "R26") (pin "P$1") (pinfunction "1_P$1") (pintype "passive"))
    )
    (net (code "104") (name "Net-(R29-1)") (class "Default")
      (node (ref "JP22") (pin "1") (pinfunction "1_1") (pintype "passive"))
      (node (ref "R29") (pin "P$1") (pinfunction "1_P$1") (pintype "passive"))
    )
    (net (code "105") (name "Net-(R32-1)") (class "Default")
      (node (ref "JP23") (pin "1") (pinfunction "1_1") (pintype "passive"))
      (node (ref "R32") (pin "P$1") (pinfunction "1_P$1") (pintype "passive"))
    )
    (net (code "106") (name "Net-(R35-1)") (class "Default")
      (node (ref "JP24") (pin "1") (pinfunction "1_1") (pintype "passive"))
      (node (ref "R35") (pin "P$1") (pinfunction "1_P$1") (pintype "passive"))
    )
    (net (code "107") (name "RES") (class "Default")
      (node (ref "JP10") (pin "1") (pinfunction "1_1") (pintype "passive"))
    )
    (net (code "108") (name "RX0") (class "Default")
      (node (ref "JP4") (pin "1") (pinfunction "1_1") (pintype "passive"))
    )
    (net (code "109") (name "SCL") (class "Default")
      (node (ref "JP5") (pin "1") (pinfunction "1_1") (pintype "passive"))
    )
    (net (code "110") (name "SCLK") (class "Default")
      (node (ref "JP26") (pin "3") (pinfunction "3_3") (pintype "passive"))
      (node (ref "JP9") (pin "16") (pinfunction "16_16") (pintype "passive"))
    )
    (net (code "111") (name "SDA") (class "Default")
      (node (ref "JP5") (pin "2") (pinfunction "2_2") (pintype "passive"))
    )
    (net (code "112") (name "SD_CS") (class "Default")
      (node (ref "JP26") (pin "4") (pinfunction "4_4") (pintype "passive"))
      (node (ref "JP8") (pin "1") (pinfunction "1_1") (pintype "passive"))
    )
    (net (code "113") (name "SIG-") (class "Default")
      (node (ref "JP25") (pin "2") (pinfunction "2_2") (pintype "passive"))
      (node (ref "JP27") (pin "3") (pinfunction "3_3") (pintype "passive"))
    )
    (net (code "114") (name "SIG-L") (class "Default")
      (node (ref "JP25") (pin "3") (pinfunction "3_3") (pintype "passive"))
      (node (ref "JP27") (pin "2") (pinfunction "2_2") (pintype "passive"))
    )
    (net (code "115") (name "SIG-R") (class "Default")
      (node (ref "JP25") (pin "1") (pinfunction "1_1") (pintype "passive"))
      (node (ref "JP27") (pin "1") (pinfunction "1_1") (pintype "passive"))
    )
    (net (code "116") (name "TX1") (class "Default")
      (node (ref "JP4") (pin "2") (pinfunction "2_2") (pintype "passive"))
    )
    (net (code "117") (name "VIN") (class "Default")
      (node (ref "JP10") (pin "6") (pinfunction "6_6") (pintype "passive"))
      (node (ref "JP25") (pin "5") (pinfunction "5_5") (pintype "passive"))
    )
    (net (code "118") (name "unconnected-(JP25-Pad4)") (class "Default")
      (node (ref "JP25") (pin "4") (pinfunction "4_4") (pintype "passive"))
    )
    (net (code "119") (name "unconnected-(JP25-Pad7)") (class "Default")
      (node (ref "JP25") (pin "7") (pinfunction "7_7") (pintype "passive"))
    )
    (net (code "120") (name "unconnected-(JP25-Pad8)") (class "Default")
      (node (ref "JP25") (pin "8") (pinfunction "8_8") (pintype "passive"))
    )
    (net (code "121") (name "unconnected-(JP25-Pad9)") (class "Default")
      (node (ref "JP25") (pin "9") (pinfunction "9_9") (pintype "passive"))
    )
  )
)
